# ComparisonSch.net
KiCad netlist of a schematic drawn in Altium Designer
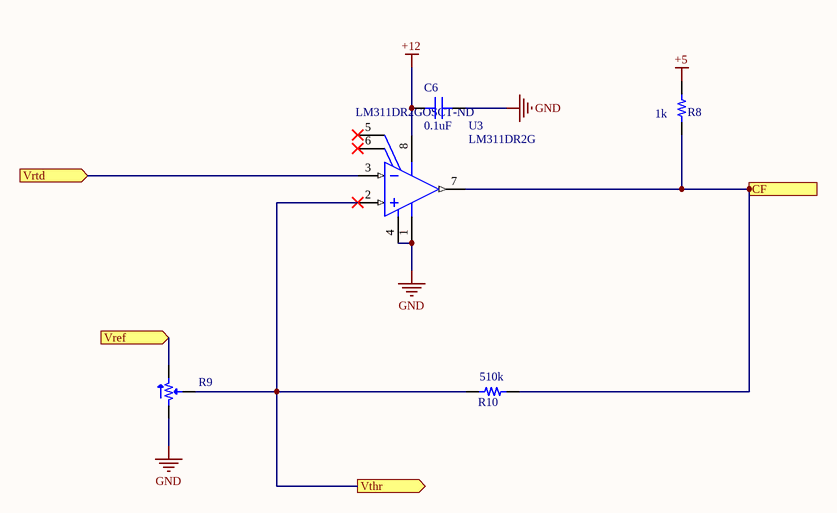
[diagram p0: ComparisonSch.SchDoc]

(export (version "E")
  (design (tool "Eeschema 10.0.6"))
  (components
    (comp (ref "C6")
      (value "0.1uF")
      (footprint "CAP 0805/2012")
      (description "CAP CER 0.1UF 25V X7R 0805")
      (fields
        (field (name "PART NUMBER") "CL21B104KACNNNC")
        (field (name "MANUFACTURER") "Samsung Electro-Mechanics America, Inc.")
      )
      (libsource (lib "Celestial Library Database") (part "Capacitor"))
    )
    (comp (ref "R8")
      (value "1k")
      (footprint "RES 1206/3216")
      (description "RES SMD 1K OHM 1% 1/4W 1206")
      (fields
        (field (name "PART NUMBER") "ERJ-8ENF1001V")
        (field (name "MANUFACTURER") "Panasonic Electronic Components")
      )
      (libsource (lib "Celestial Library Database") (part "Resistor"))
    )
    (comp (ref "R9")
      (value "20k")
      (footprint "POT MODEL91A")
      (description "TRIMMER 20K OHM 3/8\" CERMET TH")
      (fields (field (name "PART NUMBER") "91AR20KLF") (field (name "MANUFACTURER") "TT Electronics/BI"))
      (libsource (lib "Celestial Library Database") (part "Potentiometer"))
    )
    (comp (ref "R10")
      (value "510k")
      (footprint "RES 1206/3216")
      (description "RES SMD 510K OHM 5% 1/4W 1206")
      (fields
        (field (name "PART NUMBER") "ERJ-8GEYJ514V")
        (field (name "MANUFACTURER") "Panasonic Electronic Components")
      )
      (libsource (lib "Celestial Library Database") (part "Resistor"))
    )
    (comp (ref "U3")
      (value "LM311DR2G")
      (footprint "ONSC-SOIC-8-751-07_V")
      (description "Single Comparator, 5 to 30 V, 0 to 70 degC, 8-Pin SOIC, Pb-Free, Tape and Reel")
      (fields
        (field (name "MANUFACTURER") "On Semiconductor")
        (field (name "SUPPLIER PART NUMBER 1") "LM311DR2GOSCT-ND")
      )
      (libsource (lib "Altium Content Vault") (part "ONSC-LM211_311-8"))
    )
  )
  (nets
    (net (code "1") (name "+5") (class "Default")
      (node (ref "R8") (pin "2") (pinfunction "2_2") (pintype "passive"))
    )
    (net (code "2") (name "+12") (class "Default")
      (node (ref "C6") (pin "1") (pinfunction "1_1") (pintype "passive"))
      (node (ref "U3") (pin "8") (pinfunction "VCC_8") (pintype "power_in"))
    )
    (net (code "3") (name "/CF") (class "Default")
      (node (ref "R10") (pin "2") (pinfunction "2_2") (pintype "passive"))
      (node (ref "R8") (pin "1") (pinfunction "1_1") (pintype "passive"))
      (node (ref "U3") (pin "7") (pinfunction "OUT_7") (pintype "output"))
    )
    (net (code "4") (name "/Vref") (class "Default")
      (node (ref "R9") (pin "3") (pinfunction "3_3") (pintype "passive"))
    )
    (net (code "5") (name "/Vrtd") (class "Default")
      (node (ref "U3") (pin "3") (pinfunction "IN-_3") (pintype "input"))
    )
    (net (code "6") (name "/Vthr") (class "Default")
      (node (ref "R10") (pin "1") (pinfunction "1_1") (pintype "passive"))
      (node (ref "R9") (pin "2") (pinfunction "2_2") (pintype "passive"))
      (node (ref "U3") (pin "2") (pinfunction "IN+_2") (pintype "input"))
    )
    (net (code "7") (name "GND") (class "Default")
      (node (ref "C6") (pin "2") (pinfunction "2_2") (pintype "passive"))
      (node (ref "R9") (pin "1") (pinfunction "1_1") (pintype "passive"))
      (node (ref "U3") (pin "1") (pinfunction "GND_1") (pintype "power_in"))
      (node (ref "U3") (pin "4") (pinfunction "VEE_4") (pintype "power_in"))
    )
    (net (code "8") (name "unconnected-(U3-BALANCE-Pad5)") (class "Default")
      (node (ref "U3") (pin "5") (pinfunction "BALANCE_5") (pintype "passive+no_connect"))
    )
    (net (code "9") (name "unconnected-(U3-BALANCE{slash}STROBE-Pad6)") (class "Default")
      (node (ref "U3") (pin "6") (pinfunction "BALANCE/STROBE_6") (pintype "passive+no_connect"))
    )
  )
)
